# Primary_Transformer.net
KiCad netlist of a schematic drawn in Altium Designer
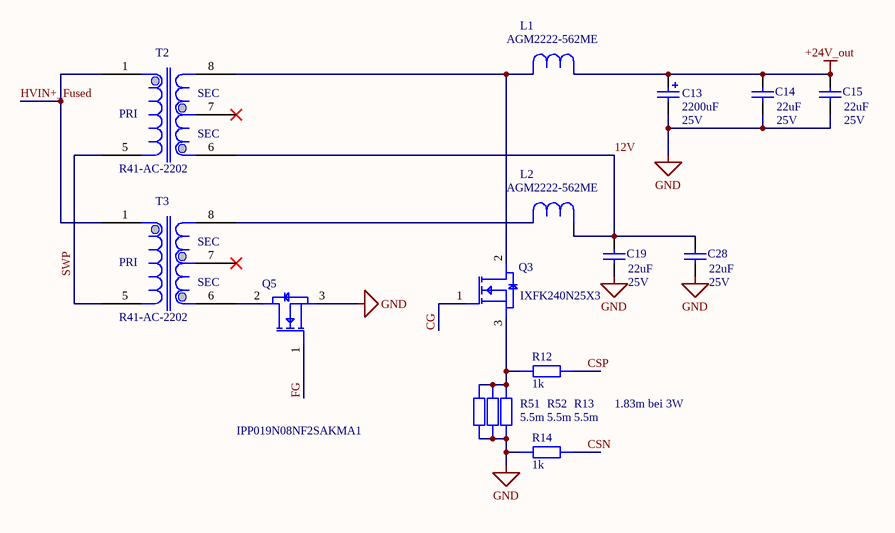
[diagram p0: Primary_Transformer.SchDoc]

(export (version "E")
  (design (tool "Eeschema 10.0.6"))
  (components
    (comp (ref "C13")
      (value "~")
      (footprint "WCAP-ATG8_D13H25")
      (description "WCAP-ATG8 Aluminum Electrolytic Capacitor, Radial, THT, D13xH25, 2200uF, 25V")
      (fields
        (field (name "MANUFACTURER PART NUMBER") "860010478021")
        (field (name "MANUFACTURER") "Wurth Elektronik")
        (field (name "CAPACITANCE") "2200uF")
        (field (name "VOLTAGE") "25V")
      )
      (libsource (lib "Altium_WCAP-ATG8 (rev20b)") (part "860010478021"))
    )
    (comp (ref "C14")
      (value "~")
      (footprint "WCAP-CSGP_1210_H=2.5mm")
      (description "WCAP-CSGP Multilayer Ceramic Chip Capacitor, General Purpose, size 1210, X5R, 22uF, 25V")
      (fields
        (field (name "MANUFACTURER PART NUMBER") "885012109014")
        (field (name "MANUFACTURER") "Wurth Elektronik")
        (field (name "CAPACITANCE") "22uF")
        (field (name "VOLTAGE") "25V")
      )
      (libsource (lib "Altium_WCAP-CSGP (rev21d)") (part "885012109014"))
    )
    (comp (ref "C15")
      (value "~")
      (footprint "WCAP-CSGP_1210_H=2.5mm")
      (description "WCAP-CSGP Multilayer Ceramic Chip Capacitor, General Purpose, size 1210, X5R, 22uF, 25V")
      (fields
        (field (name "MANUFACTURER PART NUMBER") "885012109014")
        (field (name "MANUFACTURER") "Wurth Elektronik")
        (field (name "CAPACITANCE") "22uF")
        (field (name "VOLTAGE") "25V")
      )
      (libsource (lib "Altium_WCAP-CSGP (rev21d)") (part "885012109014"))
    )
    (comp (ref "C19")
      (value "~")
      (footprint "WCAP-CSGP_1210_H=2.5mm")
      (description "WCAP-CSGP Multilayer Ceramic Chip Capacitor, General Purpose, size 1210, X5R, 22uF, 25V")
      (fields
        (field (name "MANUFACTURER PART NUMBER") "885012109014")
        (field (name "MANUFACTURER") "Wurth Elektronik")
        (field (name "CAPACITANCE") "22uF")
        (field (name "VOLTAGE") "25V")
      )
      (libsource (lib "Altium_WCAP-CSGP (rev21d)") (part "885012109014"))
    )
    (comp (ref "C28")
      (value "~")
      (footprint "WCAP-CSGP_1210_H=2.5mm")
      (description "WCAP-CSGP Multilayer Ceramic Chip Capacitor, General Purpose, size 1210, X5R, 22uF, 25V")
      (fields
        (field (name "MANUFACTURER PART NUMBER") "885012109014")
        (field (name "MANUFACTURER") "Wurth Elektronik")
        (field (name "CAPACITANCE") "22uF")
        (field (name "VOLTAGE") "25V")
      )
      (libsource (lib "Altium_WCAP-CSGP (rev21d)") (part "885012109014"))
    )
    (comp (ref "L1")
      (value "AGM2222-562ME")
      (footprint "AGM2222-562")
      (description "Shielded Power Inductors")
      (libsource (lib "Integrated_LibraryLukas_New") (part "AGM2222-562ME"))
    )
    (comp (ref "L2")
      (value "AGM2222-562ME")
      (footprint "AGM2222-562")
      (description "Shielded Power Inductors")
      (libsource (lib "Integrated_LibraryLukas_New") (part "AGM2222-562ME"))
    )
    (comp (ref "Q3")
      (value "IXFK240N25X3")
      (footprint "IXFK240N25X3_w_Cooler")
      (description "Mosfet N-ch 250V 240A TO264")
      (fields (field (name "MANUFACTURER") "IXYS"))
      (libsource (lib "Integrated_LibraryLukas_New") (part "IXFK240N25X3"))
    )
    (comp (ref "Q5")
      (value "IPP019N08NF2SAKMA1")
      (footprint "IPP019N08NF2SAKMA1_w_Cooler")
      (description "Transistor Power MOSFET N-Channel 80V 191A 3-Pin TO-220 Tube")
      (fields (field (name "MANUFACTURER") "Infineon"))
      (libsource (lib "Integrated_LibraryLukas_New") (part "IPP019N08NF2SAKMA1"))
    )
    (comp (ref "R12")
      (value "1k")
      (footprint "STACKPOLE CSR1206")
      (description "Resistor with multiple footprints")
      (fields (field (name "Comment") "SMD Resistor"))
      (libsource (lib "Standardbauteile") (part "SMD Resistor"))
    )
    (comp (ref "R13")
      (value "5.5m")
      (footprint "STACKPOLE CSR1206")
      (description "Resistor with multiple footprints")
      (libsource (lib "Standardbauteile") (part "SMD Resistor"))
    )
    (comp (ref "R14")
      (value "1k")
      (footprint "STACKPOLE CSR1206")
      (description "Resistor with multiple footprints")
      (fields (field (name "Comment") "SMD Resistor"))
      (libsource (lib "Standardbauteile") (part "SMD Resistor"))
    )
    (comp (ref "R51")
      (value "5.5m")
      (footprint "STACKPOLE CSR1206")
      (description "Resistor with multiple footprints")
      (libsource (lib "Standardbauteile") (part "SMD Resistor"))
    )
    (comp (ref "R52")
      (value "5.5m")
      (footprint "STACKPOLE CSR1206")
      (description "Resistor with multiple footprints")
      (libsource (lib "Standardbauteile") (part "SMD Resistor"))
    )
    (comp (ref "T2")
      (value "R41-AC-2202")
      (footprint "R41-AC-2202 Landing Pattern")
      (description "High Voltage Transformer")
      (libsource (lib "Integrated_LibraryLukas_New") (part "R41-AC-2202"))
    )
    (comp (ref "T3")
      (value "R41-AC-2202")
      (footprint "R41-AC-2202 Landing Pattern")
      (description "High Voltage Transformer")
      (libsource (lib "Integrated_LibraryLukas_New") (part "R41-AC-2202"))
    )
  )
  (nets
    (net (code "1") (name "+24V_out") (class "Default")
      (node (ref "C13") (pin "1") (pinfunction "P_1") (pintype "passive"))
      (node (ref "C14") (pin "1") (pinfunction "1_1") (pintype "passive"))
      (node (ref "C15") (pin "1") (pinfunction "1_1") (pintype "passive"))
      (node (ref "L1") (pin "2") (pintype "passive"))
    )
    (net (code "2") (name "/12V") (class "Default")
      (node (ref "C19") (pin "1") (pinfunction "1_1") (pintype "passive"))
      (node (ref "C28") (pin "1") (pinfunction "1_1") (pintype "passive"))
      (node (ref "L2") (pin "2") (pintype "passive"))
      (node (ref "T2") (pin "6") (pintype "passive"))
    )
    (net (code "3") (name "/CG") (class "Default") (node (ref "Q3") (pin "1") (pintype "input")))
    (net (code "4") (name "/CSN") (class "Default")
      (node (ref "R14") (pin "2") (pinfunction "2_2") (pintype "passive"))
    )
    (net (code "5") (name "/CSP") (class "Default")
      (node (ref "R12") (pin "2") (pinfunction "2_2") (pintype "passive"))
    )
    (net (code "6") (name "/FG") (class "Default") (node (ref "Q5") (pin "1") (pintype "input")))
    (net (code "7") (name "/HVIN+_Fused") (class "Default")
      (node (ref "T2") (pin "1") (pintype "passive"))
      (node (ref "T3") (pin "1") (pintype "passive"))
    )
    (net (code "8") (name "/SWP") (class "Default")
      (node (ref "T2") (pin "5") (pintype "passive"))
      (node (ref "T3") (pin "5") (pintype "passive"))
    )
    (net (code "9") (name "GND") (class "Default")
      (node (ref "C13") (pin "2") (pinfunction "N_2") (pintype "passive"))
      (node (ref "C14") (pin "2") (pinfunction "2_2") (pintype "passive"))
      (node (ref "C15") (pin "2") (pinfunction "2_2") (pintype "passive"))
      (node (ref "C19") (pin "2") (pinfunction "2_2") (pintype "passive"))
      (node (ref "C28") (pin "2") (pinfunction "2_2") (pintype "passive"))
      (node (ref "Q5") (pin "3") (pintype "input"))
      (node (ref "R13") (pin "1") (pinfunction "1_1") (pintype "passive"))
      (node (ref "R14") (pin "1") (pinfunction "1_1") (pintype "passive"))
      (node (ref "R51") (pin "1") (pinfunction "1_1") (pintype "passive"))
      (node (ref "R52") (pin "1") (pinfunction "1_1") (pintype "passive"))
    )
    (net (code "10") (name "Net-(L1-Pad1)") (class "Default")
      (node (ref "L1") (pin "1") (pintype "passive"))
      (node (ref "Q3") (pin "2") (pintype "input"))
      (node (ref "T2") (pin "8") (pintype "passive"))
    )
    (net (code "11") (name "Net-(L2-Pad1)") (class "Default")
      (node (ref "L2") (pin "1") (pintype "passive"))
      (node (ref "T3") (pin "8") (pintype "passive"))
    )
    (net (code "12") (name "Net-(Q3-Pad3)") (class "Default")
      (node (ref "Q3") (pin "3") (pintype "input"))
      (node (ref "R12") (pin "1") (pinfunction "1_1") (pintype "passive"))
      (node (ref "R13") (pin "2") (pinfunction "2_2") (pintype "passive"))
      (node (ref "R51") (pin "2") (pinfunction "2_2") (pintype "passive"))
      (node (ref "R52") (pin "2") (pinfunction "2_2") (pintype "passive"))
    )
    (net (code "13") (name "Net-(Q5-Pad2)") (class "Default")
      (node (ref "Q5") (pin "2") (pintype "input"))
      (node (ref "T3") (pin "6") (pintype "passive"))
    )
    (net (code "14") (name "unconnected-(T2-Pad7)") (class "Default")
      (node (ref "T2") (pin "7") (pintype "passive+no_connect"))
    )
    (net (code "15") (name "unconnected-(T3-Pad7)") (class "Default")
      (node (ref "T3") (pin "7") (pintype "passive+no_connect"))
    )
  )
)
